# 3340.net
KiCad netlist of a schematic drawn in EAGLE
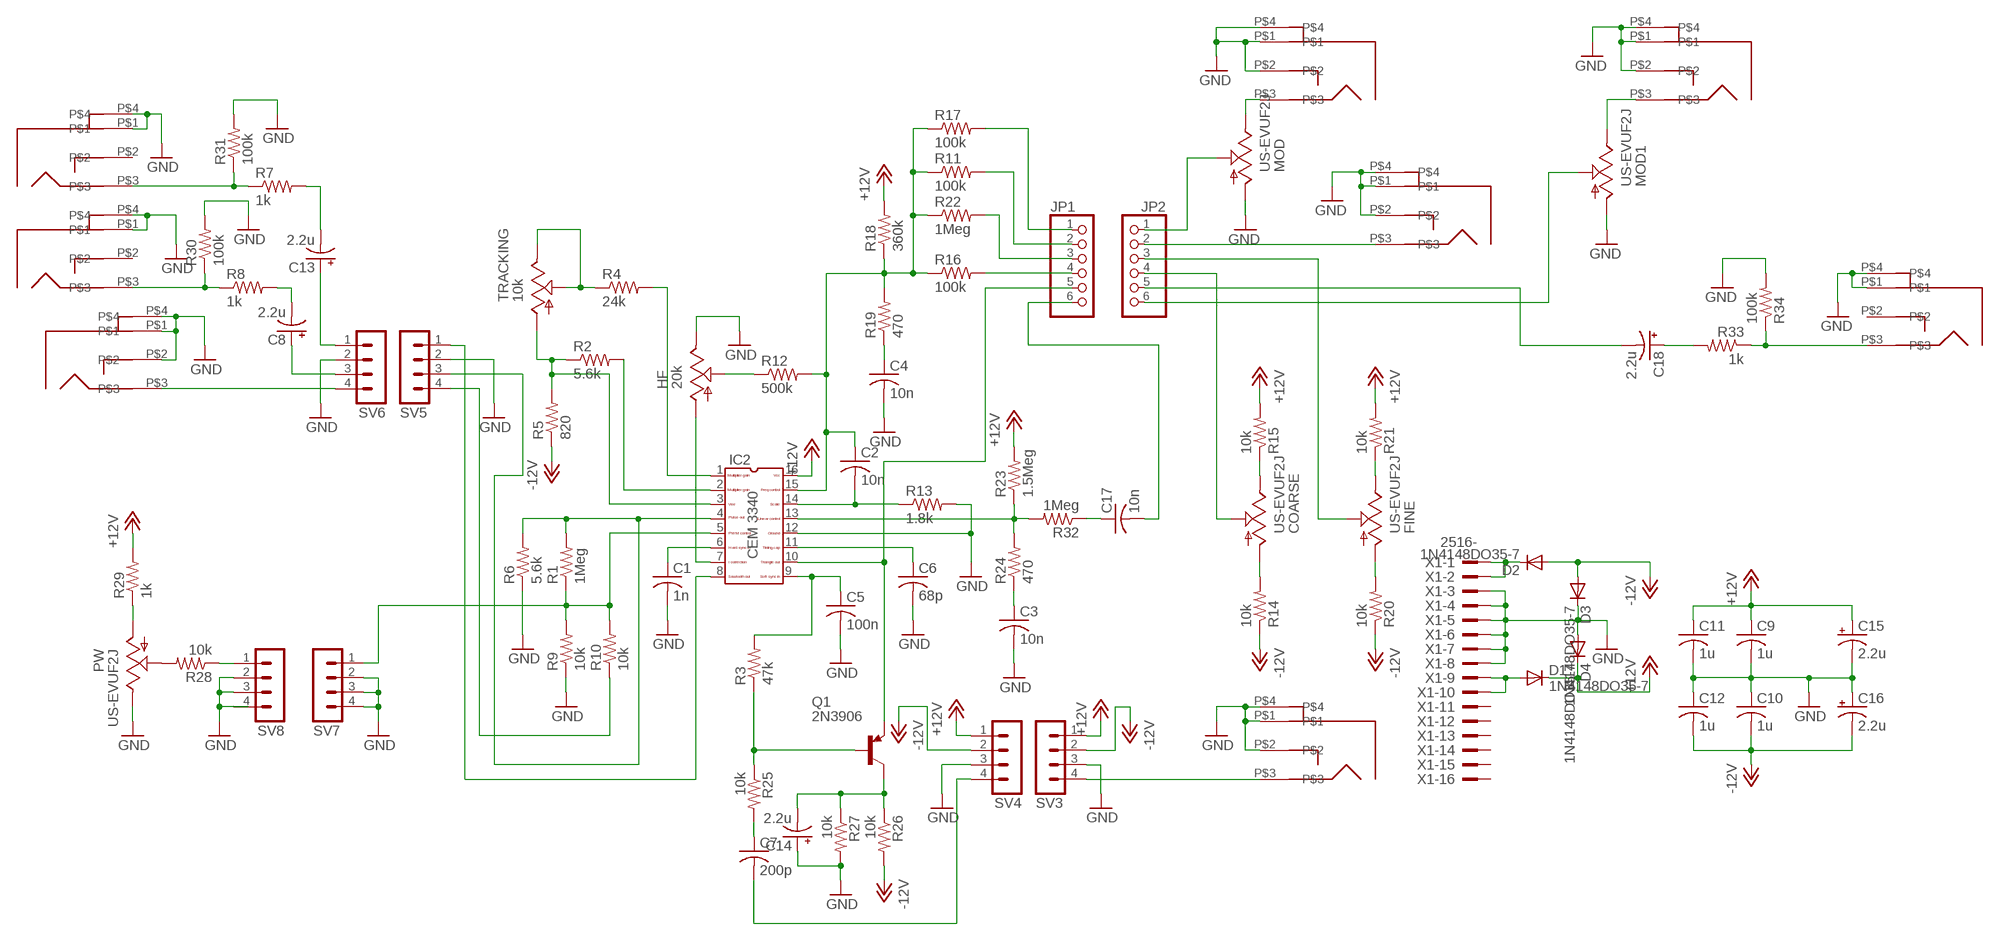
[diagram p0: schematic, sheet 1]

(export (version "E")
  (design (tool "Eeschema 10.0.6"))
  (components
    (comp (ref "C1")
      (value "1n")
      (footprint "eagle-import:C050-025X075")
      (libsource (lib "eagle-import") (part "C-US050-025X075"))
    )
    (comp (ref "C2")
      (value "10n")
      (footprint "eagle-import:C050-025X075")
      (libsource (lib "eagle-import") (part "C-US050-025X075"))
    )
    (comp (ref "C3")
      (value "10n")
      (footprint "eagle-import:C050-025X075")
      (libsource (lib "eagle-import") (part "C-US050-025X075"))
    )
    (comp (ref "C4")
      (value "10n")
      (footprint "eagle-import:C050-025X075")
      (libsource (lib "eagle-import") (part "C-US050-025X075"))
    )
    (comp (ref "C5")
      (value "100n")
      (footprint "eagle-import:C050-025X075")
      (libsource (lib "eagle-import") (part "C-US050-025X075"))
    )
    (comp (ref "C6")
      (value "68p")
      (footprint "eagle-import:C050-025X075")
      (libsource (lib "eagle-import") (part "C-US050-025X075"))
    )
    (comp (ref "C7")
      (value "200p")
      (footprint "eagle-import:C050-025X075")
      (libsource (lib "eagle-import") (part "C-US050-025X075"))
    )
    (comp (ref "C8")
      (value "2.2u")
      (footprint "eagle-import:E2,5-6")
      (libsource (lib "eagle-import") (part "CPOL-USE2.5-6"))
    )
    (comp (ref "C9")
      (value "1u")
      (footprint "eagle-import:C050-025X075")
      (libsource (lib "eagle-import") (part "C-US050-025X075"))
    )
    (comp (ref "C10")
      (value "1u")
      (footprint "eagle-import:C050-025X075")
      (libsource (lib "eagle-import") (part "C-US050-025X075"))
    )
    (comp (ref "C11")
      (value "1u")
      (footprint "eagle-import:C050-025X075")
      (libsource (lib "eagle-import") (part "C-US050-025X075"))
    )
    (comp (ref "C12")
      (value "1u")
      (footprint "eagle-import:C050-025X075")
      (libsource (lib "eagle-import") (part "C-US050-025X075"))
    )
    (comp (ref "C13")
      (value "2.2u")
      (footprint "eagle-import:E2,5-6")
      (libsource (lib "eagle-import") (part "CPOL-USE2.5-6"))
    )
    (comp (ref "C14")
      (value "2.2u")
      (footprint "eagle-import:E2,5-6")
      (libsource (lib "eagle-import") (part "CPOL-USE2.5-6"))
    )
    (comp (ref "C15")
      (value "2.2u")
      (footprint "eagle-import:E2,5-6")
      (libsource (lib "eagle-import") (part "CPOL-USE2.5-6"))
    )
    (comp (ref "C16")
      (value "2.2u")
      (footprint "eagle-import:E2,5-6")
      (libsource (lib "eagle-import") (part "CPOL-USE2.5-6"))
    )
    (comp (ref "C17")
      (value "10n")
      (footprint "eagle-import:C050-025X075")
      (libsource (lib "eagle-import") (part "C-US050-025X075"))
    )
    (comp (ref "C18")
      (value "2.2u")
      (footprint "eagle-import:E2,5-6")
      (libsource (lib "eagle-import") (part "CPOL-USE2.5-6"))
    )
    (comp (ref "COARSE")
      (value "US-EVUF2J")
      (footprint "eagle-import:EVUFXJ")
      (libsource (lib "eagle-import") (part "US-EVUF2J"))
    )
    (comp (ref "CVIN1")
      (value "PJ301BM")
      (footprint "eagle-import:PJ301BM")
      (libsource (lib "eagle-import") (part "PJ301BM"))
    )
    (comp (ref "CVIN2")
      (value "PJ301BM")
      (footprint "eagle-import:PJ301BM")
      (libsource (lib "eagle-import") (part "PJ301BM"))
    )
    (comp (ref "D1")
      (value "1N4148DO35-7")
      (footprint "eagle-import:DO35-7")
      (libsource (lib "eagle-import") (part "1N4148DO35-7"))
    )
    (comp (ref "D2")
      (value "1N4148DO35-7")
      (footprint "eagle-import:DO35-7")
      (libsource (lib "eagle-import") (part "1N4148DO35-7"))
    )
    (comp (ref "D3")
      (value "1N4148DO35-7")
      (footprint "eagle-import:DO35-7")
      (libsource (lib "eagle-import") (part "1N4148DO35-7"))
    )
    (comp (ref "D4")
      (value "1N4148DO35-7")
      (footprint "eagle-import:DO35-7")
      (libsource (lib "eagle-import") (part "1N4148DO35-7"))
    )
    (comp (ref "EXPMOD")
      (value "PJ301BM")
      (footprint "eagle-import:PJ301BM")
      (libsource (lib "eagle-import") (part "PJ301BM"))
    )
    (comp (ref "FINE")
      (value "US-EVUF2J")
      (footprint "eagle-import:EVUFXJ")
      (libsource (lib "eagle-import") (part "US-EVUF2J"))
    )
    (comp (ref "HF")
      (value "20k")
      (footprint "eagle-import:S64W")
      (libsource (lib "eagle-import") (part "TRIM_US-S64W"))
    )
    (comp (ref "IC2")
      (value "CEM3340")
      (footprint "eagle-import:DIL16")
      (libsource (lib "eagle-import") (part "CEM3340"))
    )
    (comp (ref "JP1")
      (value "PINHD-1X6")
      (footprint "eagle-import:1X06")
      (libsource (lib "eagle-import") (part "PINHD-1X6"))
    )
    (comp (ref "JP2")
      (value "PINHD-1X6")
      (footprint "eagle-import:1X06")
      (libsource (lib "eagle-import") (part "PINHD-1X6"))
    )
    (comp (ref "MOD")
      (value "US-EVUF2J")
      (footprint "eagle-import:EVUFXJ")
      (libsource (lib "eagle-import") (part "US-EVUF2J"))
    )
    (comp (ref "MOD1")
      (value "US-EVUF2J")
      (footprint "eagle-import:EVUFXJ")
      (libsource (lib "eagle-import") (part "US-EVUF2J"))
    )
    (comp (ref "PULSE")
      (value "PJ301BM")
      (footprint "eagle-import:PJ301BM")
      (libsource (lib "eagle-import") (part "PJ301BM"))
    )
    (comp (ref "PW")
      (value "US-EVUF2J")
      (footprint "eagle-import:EVUFXJ")
      (libsource (lib "eagle-import") (part "US-EVUF2J"))
    )
    (comp (ref "PWM")
      (value "PJ301BM")
      (footprint "eagle-import:PJ301BM")
      (libsource (lib "eagle-import") (part "PJ301BM"))
    )
    (comp (ref "Q1")
      (value "2N3906")
      (footprint "eagle-import:TO92")
      (libsource (lib "eagle-import") (part "2N3906"))
    )
    (comp (ref "R1")
      (value "1Meg")
      (footprint "eagle-import:0207_2V")
      (libsource (lib "eagle-import") (part "R-US_0207/2V"))
    )
    (comp (ref "R2")
      (value "5.6k")
      (footprint "eagle-import:0207_2V")
      (libsource (lib "eagle-import") (part "R-US_0207/2V"))
    )
    (comp (ref "R3")
      (value "47k")
      (footprint "eagle-import:0207_2V")
      (libsource (lib "eagle-import") (part "R-US_0207/2V"))
    )
    (comp (ref "R4")
      (value "24k")
      (footprint "eagle-import:0207_2V")
      (libsource (lib "eagle-import") (part "R-US_0207/2V"))
    )
    (comp (ref "R5")
      (value "820")
      (footprint "eagle-import:0207_2V")
      (libsource (lib "eagle-import") (part "R-US_0207/2V"))
    )
    (comp (ref "R6")
      (value "5.6k")
      (footprint "eagle-import:0207_2V")
      (libsource (lib "eagle-import") (part "R-US_0207/2V"))
    )
    (comp (ref "R7")
      (value "1k")
      (footprint "eagle-import:0207_7")
      (libsource (lib "eagle-import") (part "R-US_0207/7"))
    )
    (comp (ref "R8")
      (value "1k")
      (footprint "eagle-import:0207_7")
      (libsource (lib "eagle-import") (part "R-US_0207/7"))
    )
    (comp (ref "R9")
      (value "10k")
      (footprint "eagle-import:0207_2V")
      (libsource (lib "eagle-import") (part "R-US_0207/2V"))
    )
    (comp (ref "R10")
      (value "10k")
      (footprint "eagle-import:0207_2V")
      (libsource (lib "eagle-import") (part "R-US_0207/2V"))
    )
    (comp (ref "R11")
      (value "100k")
      (footprint "eagle-import:0207_2V")
      (libsource (lib "eagle-import") (part "R-US_0207/2V"))
    )
    (comp (ref "R12")
      (value "500k")
      (footprint "eagle-import:0207_2V")
      (libsource (lib "eagle-import") (part "R-US_0207/2V"))
    )
    (comp (ref "R13")
      (value "1.8k")
      (footprint "eagle-import:0207_2V")
      (libsource (lib "eagle-import") (part "R-US_0207/2V"))
    )
    (comp (ref "R14")
      (value "10k")
      (footprint "eagle-import:0207_7")
      (libsource (lib "eagle-import") (part "R-US_0207/7"))
    )
    (comp (ref "R15")
      (value "10k")
      (footprint "eagle-import:0207_7")
      (libsource (lib "eagle-import") (part "R-US_0207/7"))
    )
    (comp (ref "R16")
      (value "100k")
      (footprint "eagle-import:0207_2V")
      (libsource (lib "eagle-import") (part "R-US_0207/2V"))
    )
    (comp (ref "R17")
      (value "100k")
      (footprint "eagle-import:0207_2V")
      (libsource (lib "eagle-import") (part "R-US_0207/2V"))
    )
    (comp (ref "R18")
      (value "360k")
      (footprint "eagle-import:0207_2V")
      (libsource (lib "eagle-import") (part "R-US_0207/2V"))
    )
    (comp (ref "R19")
      (value "470")
      (footprint "eagle-import:0207_2V")
      (libsource (lib "eagle-import") (part "R-US_0207/2V"))
    )
    (comp (ref "R20")
      (value "10k")
      (footprint "eagle-import:0207_7")
      (libsource (lib "eagle-import") (part "R-US_0207/7"))
    )
    (comp (ref "R21")
      (value "10k")
      (footprint "eagle-import:0207_7")
      (libsource (lib "eagle-import") (part "R-US_0207/7"))
    )
    (comp (ref "R22")
      (value "1Meg")
      (footprint "eagle-import:0207_2V")
      (libsource (lib "eagle-import") (part "R-US_0207/2V"))
    )
    (comp (ref "R23")
      (value "1.5Meg")
      (footprint "eagle-import:0207_2V")
      (libsource (lib "eagle-import") (part "R-US_0207/2V"))
    )
    (comp (ref "R24")
      (value "470")
      (footprint "eagle-import:0207_2V")
      (libsource (lib "eagle-import") (part "R-US_0207/2V"))
    )
    (comp (ref "R25")
      (value "10k")
      (footprint "eagle-import:0207_2V")
      (libsource (lib "eagle-import") (part "R-US_0207/2V"))
    )
    (comp (ref "R26")
      (value "10k")
      (footprint "eagle-import:0207_2V")
      (libsource (lib "eagle-import") (part "R-US_0207/2V"))
    )
    (comp (ref "R27")
      (value "10k")
      (footprint "eagle-import:0207_2V")
      (libsource (lib "eagle-import") (part "R-US_0207/2V"))
    )
    (comp (ref "R28")
      (value "10k")
      (footprint "eagle-import:0207_7")
      (libsource (lib "eagle-import") (part "R-US_0207/7"))
    )
    (comp (ref "R29")
      (value "1k")
      (footprint "eagle-import:0207_7")
      (libsource (lib "eagle-import") (part "R-US_0207/7"))
    )
    (comp (ref "R30")
      (value "100k")
      (footprint "eagle-import:0207_7")
      (libsource (lib "eagle-import") (part "R-US_0207/7"))
    )
    (comp (ref "R31")
      (value "100k")
      (footprint "eagle-import:0207_7")
      (libsource (lib "eagle-import") (part "R-US_0207/7"))
    )
    (comp (ref "R32")
      (value "1Meg")
      (footprint "eagle-import:0207_2V")
      (libsource (lib "eagle-import") (part "R-US_0207/2V"))
    )
    (comp (ref "R33")
      (value "1k")
      (footprint "eagle-import:0207_7")
      (libsource (lib "eagle-import") (part "R-US_0207/7"))
    )
    (comp (ref "R34")
      (value "100k")
      (footprint "eagle-import:0207_7")
      (libsource (lib "eagle-import") (part "R-US_0207/7"))
    )
    (comp (ref "SAW")
      (value "PJ301BM")
      (footprint "eagle-import:PJ301BM")
      (libsource (lib "eagle-import") (part "PJ301BM"))
    )
    (comp (ref "SAW1")
      (value "PJ301BM")
      (footprint "eagle-import:PJ301BM")
      (libsource (lib "eagle-import") (part "PJ301BM"))
    )
    (comp (ref "SV3")
      (value "MA04-1")
      (footprint "eagle-import:MA04-1")
      (libsource (lib "eagle-import") (part "MA04-1"))
    )
    (comp (ref "SV4")
      (value "MA04-1")
      (footprint "eagle-import:MA04-1")
      (libsource (lib "eagle-import") (part "MA04-1"))
    )
    (comp (ref "SV5")
      (value "MA04-1")
      (footprint "eagle-import:MA04-1")
      (libsource (lib "eagle-import") (part "MA04-1"))
    )
    (comp (ref "SV6")
      (value "MA04-1")
      (footprint "eagle-import:MA04-1")
      (libsource (lib "eagle-import") (part "MA04-1"))
    )
    (comp (ref "SV7")
      (value "MA04-1")
      (footprint "eagle-import:MA04-1")
      (libsource (lib "eagle-import") (part "MA04-1"))
    )
    (comp (ref "SV8")
      (value "MA04-1")
      (footprint "eagle-import:MA04-1")
      (libsource (lib "eagle-import") (part "MA04-1"))
    )
    (comp (ref "SYNC")
      (value "PJ301BM")
      (footprint "eagle-import:PJ301BM")
      (libsource (lib "eagle-import") (part "PJ301BM"))
    )
    (comp (ref "TRACKING")
      (value "10k")
      (footprint "eagle-import:S64W")
      (libsource (lib "eagle-import") (part "TRIM_US-S64W"))
    )
    (comp (ref "X1")
      (value "2516-")
      (footprint "eagle-import:PAK100_2500-16")
      (libsource (lib "eagle-import") (part "2516-"))
    )
  )
  (nets
    (net (code "1") (name "+12V") (class "Default")
      (node (ref "C11") (pin "1") (pinfunction "1_1") (pintype "passive"))
      (node (ref "C15") (pin "+") (pinfunction "+_+") (pintype "passive"))
      (node (ref "C9") (pin "1") (pinfunction "1_1") (pintype "passive"))
      (node (ref "D1") (pin "C") (pinfunction "C_C") (pintype "passive"))
      (node (ref "D4") (pin "C") (pinfunction "C_C") (pintype "passive"))
      (node (ref "IC2") (pin "16") (pinfunction "16_16") (pintype "power_in"))
      (node (ref "R15") (pin "2") (pinfunction "2_2") (pintype "passive"))
      (node (ref "R18") (pin "2") (pinfunction "2_2") (pintype "passive"))
      (node (ref "R21") (pin "2") (pinfunction "2_2") (pintype "passive"))
      (node (ref "R23") (pin "2") (pinfunction "2_2") (pintype "passive"))
      (node (ref "R29") (pin "2") (pinfunction "2_2") (pintype "passive"))
      (node (ref "SV3") (pin "1") (pinfunction "1_1") (pintype "passive"))
      (node (ref "SV4") (pin "1") (pinfunction "1_1") (pintype "passive"))
    )
    (net (code "2") (name "-12V") (class "Default")
      (node (ref "C10") (pin "2") (pinfunction "2_2") (pintype "passive"))
      (node (ref "C12") (pin "2") (pinfunction "2_2") (pintype "passive"))
      (node (ref "C16") (pin "-") (pinfunction "-_-") (pintype "passive"))
      (node (ref "D2") (pin "A") (pinfunction "A_A") (pintype "passive"))
      (node (ref "D3") (pin "A") (pinfunction "A_A") (pintype "passive"))
      (node (ref "R14") (pin "1") (pinfunction "1_1") (pintype "passive"))
      (node (ref "R20") (pin "1") (pinfunction "1_1") (pintype "passive"))
      (node (ref "R26") (pin "2") (pinfunction "2_2") (pintype "passive"))
      (node (ref "R5") (pin "1") (pinfunction "1_1") (pintype "passive"))
      (node (ref "SV3") (pin "2") (pinfunction "2_2") (pintype "passive"))
      (node (ref "SV4") (pin "2") (pinfunction "2_2") (pintype "passive"))
    )
    (net (code "3") (name "GND") (class "Default")
      (node (ref "C1") (pin "2") (pinfunction "2_2") (pintype "passive"))
      (node (ref "C10") (pin "1") (pinfunction "1_1") (pintype "passive"))
      (node (ref "C11") (pin "2") (pinfunction "2_2") (pintype "passive"))
      (node (ref "C12") (pin "1") (pinfunction "1_1") (pintype "passive"))
      (node (ref "C14") (pin "+") (pinfunction "+_+") (pintype "passive"))
      (node (ref "C15") (pin "-") (pinfunction "-_-") (pintype "passive"))
      (node (ref "C16") (pin "+") (pinfunction "+_+") (pintype "passive"))
      (node (ref "C3") (pin "2") (pinfunction "2_2") (pintype "passive"))
      (node (ref "C4") (pin "2") (pinfunction "2_2") (pintype "passive"))
      (node (ref "C5") (pin "2") (pinfunction "2_2") (pintype "passive"))
      (node (ref "C6") (pin "2") (pinfunction "2_2") (pintype "passive"))
      (node (ref "C9") (pin "2") (pinfunction "2_2") (pintype "passive"))
      (node (ref "CVIN1") (pin "P$1") (pinfunction "P$1_P$1") (pintype "bidirectional"))
      (node (ref "CVIN1") (pin "P$2") (pinfunction "P$2_P$2") (pintype "bidirectional"))
      (node (ref "CVIN1") (pin "P$4") (pinfunction "P$4_P$4") (pintype "bidirectional"))
      (node (ref "CVIN2") (pin "P$1") (pinfunction "P$1_P$1") (pintype "bidirectional"))
      (node (ref "CVIN2") (pin "P$2") (pinfunction "P$2_P$2") (pintype "bidirectional"))
      (node (ref "CVIN2") (pin "P$4") (pinfunction "P$4_P$4") (pintype "bidirectional"))
      (node (ref "D3") (pin "C") (pinfunction "C_C") (pintype "passive"))
      (node (ref "D4") (pin "A") (pinfunction "A_A") (pintype "passive"))
      (node (ref "EXPMOD") (pin "P$1") (pinfunction "P$1_P$1") (pintype "bidirectional"))
      (node (ref "EXPMOD") (pin "P$2") (pinfunction "P$2_P$2") (pintype "bidirectional"))
      (node (ref "EXPMOD") (pin "P$4") (pinfunction "P$4_P$4") (pintype "bidirectional"))
      (node (ref "HF") (pin "E") (pinfunction "E_E") (pintype "passive"))
      (node (ref "IC2") (pin "12") (pinfunction "12_12") (pintype "power_in"))
      (node (ref "MOD") (pin "1") (pinfunction "A_1") (pintype "passive"))
      (node (ref "MOD1") (pin "1") (pinfunction "A_1") (pintype "passive"))
      (node (ref "PULSE") (pin "P$1") (pinfunction "P$1_P$1") (pintype "bidirectional"))
      (node (ref "PULSE") (pin "P$4") (pinfunction "P$4_P$4") (pintype "bidirectional"))
      (node (ref "PW") (pin "3") (pinfunction "E_3") (pintype "passive"))
      (node (ref "PWM") (pin "P$1") (pinfunction "P$1_P$1") (pintype "bidirectional"))
      (node (ref "PWM") (pin "P$2") (pinfunction "P$2_P$2") (pintype "bidirectional"))
      (node (ref "PWM") (pin "P$4") (pinfunction "P$4_P$4") (pintype "bidirectional"))
      (node (ref "R13") (pin "2") (pinfunction "2_2") (pintype "passive"))
      (node (ref "R27") (pin "2") (pinfunction "2_2") (pintype "passive"))
      (node (ref "R30") (pin "2") (pinfunction "2_2") (pintype "passive"))
      (node (ref "R31") (pin "2") (pinfunction "2_2") (pintype "passive"))
      (node (ref "R34") (pin "2") (pinfunction "2_2") (pintype "passive"))
      (node (ref "R6") (pin "1") (pinfunction "1_1") (pintype "passive"))
      (node (ref "R9") (pin "1") (pinfunction "1_1") (pintype "passive"))
      (node (ref "SAW") (pin "P$1") (pinfunction "P$1_P$1") (pintype "bidirectional"))
      (node (ref "SAW") (pin "P$4") (pinfunction "P$4_P$4") (pintype "bidirectional"))
      (node (ref "SAW1") (pin "P$1") (pinfunction "P$1_P$1") (pintype "bidirectional"))
      (node (ref "SAW1") (pin "P$4") (pinfunction "P$4_P$4") (pintype "bidirectional"))
      (node (ref "SV3") (pin "3") (pinfunction "3_3") (pintype "passive"))
      (node (ref "SV4") (pin "3") (pinfunction "3_3") (pintype "passive"))
      (node (ref "SV5") (pin "2") (pinfunction "2_2") (pintype "passive"))
      (node (ref "SV6") (pin "2") (pinfunction "2_2") (pintype "passive"))
      (node (ref "SV7") (pin "2") (pinfunction "2_2") (pintype "passive"))
      (node (ref "SV7") (pin "3") (pinfunction "3_3") (pintype "passive"))
      (node (ref "SV7") (pin "4") (pinfunction "4_4") (pintype "passive"))
      (node (ref "SV8") (pin "2") (pinfunction "2_2") (pintype "passive"))
      (node (ref "SV8") (pin "3") (pinfunction "3_3") (pintype "passive"))
      (node (ref "SYNC") (pin "P$1") (pinfunction "P$1_P$1") (pintype "bidirectional"))
      (node (ref "SYNC") (pin "P$2") (pinfunction "P$2_P$2") (pintype "bidirectional"))
      (node (ref "SYNC") (pin "P$4") (pinfunction "P$4_P$4") (pintype "bidirectional"))
      (node (ref "X1") (pin "3") (pinfunction "KL_3") (pintype "passive"))
      (node (ref "X1") (pin "4") (pinfunction "KL_4") (pintype "passive"))
      (node (ref "X1") (pin "5") (pinfunction "KL_5") (pintype "passive"))
      (node (ref "X1") (pin "6") (pinfunction "KL_6") (pintype "passive"))
      (node (ref "X1") (pin "7") (pinfunction "KL_7") (pintype "passive"))
      (node (ref "X1") (pin "8") (pinfunction "KL_8") (pintype "passive"))
    )
    (net (code "4") (name "Net-(C1-Pad1)") (class "Default")
      (node (ref "C1") (pin "1") (pinfunction "1_1") (pintype "passive"))
      (node (ref "IC2") (pin "6") (pinfunction "6_6") (pintype "input"))
    )
    (net (code "5") (name "Net-(C2-Pad1)") (class "Default")
      (node (ref "C2") (pin "1") (pinfunction "1_1") (pintype "passive"))
      (node (ref "IC2") (pin "15") (pinfunction "15_15") (pintype "input"))
      (node (ref "R11") (pin "1") (pinfunction "1_1") (pintype "passive"))
      (node (ref "R12") (pin "2") (pinfunction "2_2") (pintype "passive"))
      (node (ref "R16") (pin "1") (pinfunction "1_1") (pintype "passive"))
      (node (ref "R17") (pin "1") (pinfunction "1_1") (pintype "passive"))
      (node (ref "R18") (pin "1") (pinfunction "1_1") (pintype "passive"))
      (node (ref "R19") (pin "2") (pinfunction "2_2") (pintype "passive"))
      (node (ref "R22") (pin "1") (pinfunction "1_1") (pintype "passive"))
    )
    (net (code "6") (name "Net-(C2-Pad2)") (class "Default")
      (node (ref "C2") (pin "2") (pinfunction "2_2") (pintype "passive"))
      (node (ref "IC2") (pin "14") (pinfunction "14_14") (pintype "input"))
      (node (ref "R13") (pin "1") (pinfunction "1_1") (pintype "passive"))
    )
    (net (code "7") (name "Net-(C3-Pad1)") (class "Default")
      (node (ref "C3") (pin "1") (pinfunction "1_1") (pintype "passive"))
      (node (ref "R24") (pin "1") (pinfunction "1_1") (pintype "passive"))
    )
    (net (code "8") (name "Net-(C4-Pad1)") (class "Default")
      (node (ref "C4") (pin "1") (pinfunction "1_1") (pintype "passive"))
      (node (ref "R19") (pin "1") (pinfunction "1_1") (pintype "passive"))
    )
    (net (code "9") (name "Net-(C5-Pad1)") (class "Default")
      (node (ref "C5") (pin "1") (pinfunction "1_1") (pintype "passive"))
      (node (ref "IC2") (pin "9") (pinfunction "9_9") (pintype "input"))
      (node (ref "R3") (pin "2") (pinfunction "2_2") (pintype "passive"))
    )
    (net (code "10") (name "Net-(C6-Pad1)") (class "Default")
      (node (ref "C6") (pin "1") (pinfunction "1_1") (pintype "passive"))
      (node (ref "IC2") (pin "11") (pinfunction "11_11") (pintype "bidirectional"))
    )
    (net (code "11") (name "Net-(C7-Pad1)") (class "Default")
      (node (ref "C7") (pin "1") (pinfunction "1_1") (pintype "passive"))
      (node (ref "R25") (pin "2") (pinfunction "2_2") (pintype "passive"))
    )
    (net (code "12") (name "Net-(C7-Pad2)") (class "Default")
      (node (ref "C7") (pin "2") (pinfunction "2_2") (pintype "passive"))
      (node (ref "SV4") (pin "4") (pinfunction "4_4") (pintype "passive"))
    )
    (net (code "13") (name "Net-(C8-Pad+)") (class "Default")
      (node (ref "C8") (pin "+") (pinfunction "+_+") (pintype "passive"))
      (node (ref "SV6") (pin "3") (pinfunction "3_3") (pintype "passive"))
    )
    (net (code "14") (name "Net-(C8-Pad-)") (class "Default")
      (node (ref "C8") (pin "-") (pinfunction "-_-") (pintype "passive"))
      (node (ref "R8") (pin "2") (pinfunction "2_2") (pintype "passive"))
    )
    (net (code "15") (name "Net-(C13-Pad+)") (class "Default")
      (node (ref "C13") (pin "+") (pinfunction "+_+") (pintype "passive"))
      (node (ref "SV6") (pin "1") (pinfunction "1_1") (pintype "passive"))
    )
    (net (code "16") (name "Net-(C13-Pad-)") (class "Default")
      (node (ref "C13") (pin "-") (pinfunction "-_-") (pintype "passive"))
      (node (ref "R7") (pin "2") (pinfunction "2_2") (pintype "passive"))
    )
    (net (code "17") (name "Net-(C17-Pad1)") (class "Default")
      (node (ref "C17") (pin "1") (pinfunction "1_1") (pintype "passive"))
      (node (ref "R32") (pin "1") (pinfunction "1_1") (pintype "passive"))
    )
    (net (code "18") (name "Net-(C17-Pad2)") (class "Default")
      (node (ref "C17") (pin "2") (pinfunction "2_2") (pintype "passive"))
      (node (ref "JP1") (pin "6") (pinfunction "6_6") (pintype "passive"))
    )
    (net (code "19") (name "Net-(C18-Pad+)") (class "Default")
      (node (ref "C18") (pin "+") (pinfunction "+_+") (pintype "passive"))
      (node (ref "R33") (pin "2") (pinfunction "2_2") (pintype "passive"))
    )
    (net (code "20") (name "Net-(C18-Pad-)") (class "Default")
      (node (ref "C18") (pin "-") (pinfunction "-_-") (pintype "passive"))
      (node (ref "JP2") (pin "5") (pinfunction "5_5") (pintype "passive"))
    )
    (net (code "21") (name "Net-(COARSE-A)") (class "Default")
      (node (ref "COARSE") (pin "1") (pinfunction "A_1") (pintype "passive"))
      (node (ref "R14") (pin "2") (pinfunction "2_2") (pintype "passive"))
    )
    (net (code "22") (name "Net-(COARSE-E)") (class "Default")
      (node (ref "COARSE") (pin "3") (pinfunction "E_3") (pintype "passive"))
      (node (ref "R15") (pin "1") (pinfunction "1_1") (pintype "passive"))
    )
    (net (code "23") (name "Net-(COARSE-S)") (class "Default")
      (node (ref "COARSE") (pin "2") (pinfunction "S_2") (pintype "passive"))
      (node (ref "JP2") (pin "4") (pinfunction "4_4") (pintype "passive"))
    )
    (net (code "24") (name "Net-(CVIN1-PadP$3)") (class "Default")
      (node (ref "CVIN1") (pin "P$3") (pinfunction "P$3_P$3") (pintype "bidirectional"))
      (node (ref "JP2") (pin "2") (pinfunction "2_2") (pintype "passive"))
    )
    (net (code "25") (name "Net-(FINE-A)") (class "Default")
      (node (ref "FINE") (pin "1") (pinfunction "A_1") (pintype "passive"))
      (node (ref "R20") (pin "2") (pinfunction "2_2") (pintype "passive"))
    )
    (net (code "26") (name "Net-(FINE-E)") (class "Default")
      (node (ref "FINE") (pin "3") (pinfunction "E_3") (pintype "passive"))
      (node (ref "R21") (pin "1") (pinfunction "1_1") (pintype "passive"))
    )
    (net (code "27") (name "Net-(FINE-S)") (class "Default")
      (node (ref "FINE") (pin "2") (pinfunction "S_2") (pintype "passive"))
      (node (ref "JP2") (pin "3") (pinfunction "3_3") (pintype "passive"))
    )
    (net (code "28") (name "Net-(HF-PadA)") (class "Default")
      (node (ref "HF") (pin "A") (pinfunction "A_A") (pintype "passive"))
      (node (ref "IC2") (pin "7") (pinfunction "7_7") (pintype "bidirectional"))
    )
    (net (code "29") (name "Net-(HF-PadS)") (class "Default")
      (node (ref "HF") (pin "S") (pinfunction "S_S") (pintype "passive"))
      (node (ref "R12") (pin "1") (pinfunction "1_1") (pintype "passive"))
    )
    (net (code "30") (name "Net-(IC2-Pad1)") (class "Default")
      (node (ref "IC2") (pin "1") (pinfunction "1_1") (pintype "bidirectional"))
      (node (ref "R4") (pin "2") (pinfunction "2_2") (pintype "passive"))
    )
    (net (code "31") (name "Net-(IC2-Pad2)") (class "Default")
      (node (ref "IC2") (pin "2") (pinfunction "2_2") (pintype "bidirectional"))
      (node (ref "R2") (pin "2") (pinfunction "2_2") (pintype "passive"))
    )
    (net (code "32") (name "Net-(IC2-Pad3)") (class "Default")
      (node (ref "IC2") (pin "3") (pinfunction "3_3") (pintype "power_in"))
      (node (ref "R2") (pin "1") (pinfunction "1_1") (pintype "passive"))
      (node (ref "R5") (pin "2") (pinfunction "2_2") (pintype "passive"))
      (node (ref "TRACKING") (pin "A") (pinfunction "A_A") (pintype "passive"))
    )
    (net (code "33") (name "Net-(IC2-Pad4)") (class "Default")
      (node (ref "IC2") (pin "4") (pinfunction "4_4") (pintype "output"))
      (node (ref "R1") (pin "2") (pinfunction "2_2") (pintype "passive"))
      (node (ref "R6") (pin "2") (pinfunction "2_2") (pintype "passive"))
      (node (ref "SV5") (pin "3") (pinfunction "3_3") (pintype "passive"))
    )
    (net (code "34") (name "Net-(IC2-Pad5)") (class "Default")
      (node (ref "IC2") (pin "5") (pinfunction "5_5") (pintype "input"))
      (node (ref "R1") (pin "1") (pinfunction "1_1") (pintype "passive"))
      (node (ref "R10") (pin "2") (pinfunction "2_2") (pintype "passive"))
      (node (ref "R9") (pin "2") (pinfunction "2_2") (pintype "passive"))
      (node (ref "SV7") (pin "1") (pinfunction "1_1") (pintype "passive"))
    )
    (net (code "35") (name "Net-(IC2-Pad8)") (class "Default")
      (node (ref "IC2") (pin "8") (pinfunction "8_8") (pintype "output"))
      (node (ref "SV5") (pin "1") (pinfunction "1_1") (pintype "passive"))
    )
    (net (code "36") (name "Net-(IC2-Pad13)") (class "Default")
      (node (ref "IC2") (pin "13") (pinfunction "13_13") (pintype "input"))
      (node (ref "R23") (pin "1") (pinfunction "1_1") (pintype "passive"))
      (node (ref "R24") (pin "2") (pinfunction "2_2") (pintype "passive"))
      (node (ref "R32") (pin "2") (pinfunction "2_2") (pintype "passive"))
    )
    (net (code "37") (name "Net-(JP1-Pad1)") (class "Default")
      (node (ref "JP1") (pin "1") (pinfunction "1_1") (pintype "passive"))
      (node (ref "R17") (pin "2") (pinfunction "2_2") (pintype "passive"))
    )
    (net (code "38") (name "Net-(JP1-Pad2)") (class "Default")
      (node (ref "JP1") (pin "2") (pinfunction "2_2") (pintype "passive"))
      (node (ref "R11") (pin "2") (pinfunction "2_2") (pintype "passive"))
    )
    (net (code "39") (name "Net-(JP1-Pad3)") (class "Default")
      (node (ref "JP1") (pin "3") (pinfunction "3_3") (pintype "passive"))
      (node (ref "R22") (pin "2") (pinfunction "2_2") (pintype "passive"))
    )
    (net (code "40") (name "Net-(JP1-Pad4)") (class "Default")
      (node (ref "JP1") (pin "4") (pinfunction "4_4") (pintype "passive"))
      (node (ref "R16") (pin "2") (pinfunction "2_2") (pintype "passive"))
    )
    (net (code "41") (name "Net-(MOD-E)") (class "Default")
      (node (ref "EXPMOD") (pin "P$3") (pinfunction "P$3_P$3") (pintype "bidirectional"))
      (node (ref "MOD") (pin "3") (pinfunction "E_3") (pintype "passive"))
    )
    (net (code "42") (name "Net-(MOD-S)") (class "Default")
      (node (ref "JP2") (pin "1") (pinfunction "1_1") (pintype "passive"))
      (node (ref "MOD") (pin "2") (pinfunction "S_2") (pintype "passive"))
    )
    (net (code "43") (name "Net-(MOD1-E)") (class "Default")
      (node (ref "CVIN2") (pin "P$3") (pinfunction "P$3_P$3") (pintype "bidirectional"))
      (node (ref "MOD1") (pin "3") (pinfunction "E_3") (pintype "passive"))
    )
    (net (code "44") (name "Net-(MOD1-S)") (class "Default")
      (node (ref "JP2") (pin "6") (pinfunction "6_6") (pintype "passive"))
      (node (ref "MOD1") (pin "2") (pinfunction "S_2") (pintype "passive"))
    )
    (net (code "45") (name "Net-(PULSE-PadP$3)") (class "Default")
      (node (ref "PULSE") (pin "P$3") (pinfunction "P$3_P$3") (pintype "bidirectional"))
      (node (ref "R30") (pin "1") (pinfunction "1_1") (pintype "passive"))
      (node (ref "R8") (pin "1") (pinfunction "1_1") (pintype "passive"))
    )
    (net (code "46") (name "Net-(PW-A)") (class "Default")
      (node (ref "PW") (pin "1") (pinfunction "A_1") (pintype "passive"))
      (node (ref "R29") (pin "1") (pinfunction "1_1") (pintype "passive"))
    )
    (net (code "47") (name "Net-(PW-S)") (class "Default")
      (node (ref "PW") (pin "2") (pinfunction "S_2") (pintype "passive"))
      (node (ref "R28") (pin "2") (pinfunction "2_2") (pintype "passive"))
    )
    (net (code "48") (name "Net-(PWM-PadP$3)") (class "Default")
      (node (ref "PWM") (pin "P$3") (pinfunction "P$3_P$3") (pintype "bidirectional"))
      (node (ref "SV6") (pin "4") (pinfunction "4_4") (pintype "passive"))
    )
    (net (code "49") (name "Net-(Q1-B)") (class "Default")
      (node (ref "Q1") (pin "2") (pinfunction "B_2") (pintype "passive"))
      (node (ref "R25") (pin "1") (pinfunction "1_1") (pintype "passive"))
      (node (ref "R3") (pin "1") (pinfunction "1_1") (pintype "passive"))
    )
    (net (code "50") (name "Net-(Q1-C)") (class "Default")
      (node (ref "C14") (pin "-") (pinfunction "-_-") (pintype "passive"))
      (node (ref "Q1") (pin "1") (pinfunction "C_1") (pintype "passive"))
      (node (ref "R26") (pin "1") (pinfunction "1_1") (pintype "passive"))
      (node (ref "R27") (pin "1") (pinfunction "1_1") (pintype "passive"))
    )
    (net (code "51") (name "Net-(Q1-E)") (class "Default")
      (node (ref "IC2") (pin "10") (pinfunction "10_10") (pintype "output"))
      (node (ref "JP1") (pin "5") (pinfunction "5_5") (pintype "passive"))
      (node (ref "Q1") (pin "3") (pinfunction "E_3") (pintype "passive"))
    )
    (net (code "52") (name "Net-(R4-Pad1)") (class "Default")
      (node (ref "R4") (pin "1") (pinfunction "1_1") (pintype "passive"))
      (node (ref "TRACKING") (pin "E") (pinfunction "E_E") (pintype "passive"))
      (node (ref "TRACKING") (pin "S") (pinfunction "S_S") (pintype "passive"))
    )
    (net (code "53") (name "Net-(R10-Pad1)") (class "Default")
      (node (ref "R10") (pin "1") (pinfunction "1_1") (pintype "passive"))
      (node (ref "SV5") (pin "4") (pinfunction "4_4") (pintype "passive"))
    )
    (net (code "54") (name "Net-(R28-Pad1)") (class "Default")
      (node (ref "R28") (pin "1") (pinfunction "1_1") (pintype "passive"))
      (node (ref "SV8") (pin "1") (pinfunction "1_1") (pintype "passive"))
    )
    (net (code "55") (name "Net-(R31-Pad1)") (class "Default")
      (node (ref "R31") (pin "1") (pinfunction "1_1") (pintype "passive"))
      (node (ref "R7") (pin "1") (pinfunction "1_1") (pintype "passive"))
      (node (ref "SAW") (pin "P$3") (pinfunction "P$3_P$3") (pintype "bidirectional"))
    )
    (net (code "56") (name "Net-(R33-Pad1)") (class "Default")
      (node (ref "R33") (pin "1") (pinfunction "1_1") (pintype "passive"))
      (node (ref "R34") (pin "1") (pinfunction "1_1") (pintype "passive"))
      (node (ref "SAW1") (pin "P$3") (pinfunction "P$3_P$3") (pintype "bidirectional"))
    )
    (net (code "57") (name "Net-(SV3-Pad4)") (class "Default")
      (node (ref "SV3") (pin "4") (pinfunction "4_4") (pintype "passive"))
      (node (ref "SYNC") (pin "P$3") (pinfunction "P$3_P$3") (pintype "bidirectional"))
    )
    (net (code "58") (name "Net-(X1A-KL)") (class "Default")
      (node (ref "D2") (pin "C") (pinfunction "C_C") (pintype "passive"))
      (node (ref "X1") (pin "1") (pinfunction "KL_1") (pintype "passive"))
      (node (ref "X1") (pin "2") (pinfunction "KL_2") (pintype "passive"))
    )
    (net (code "59") (name "Net-(X1B-KL)") (class "Default")
      (node (ref "D1") (pin "A") (pinfunction "A_A") (pintype "passive"))
      (node (ref "X1") (pin "10") (pinfunction "KL_10") (pintype "passive"))
      (node (ref "X1") (pin "9") (pinfunction "KL_9") (pintype "passive"))
    )
    (net (code "60") (name "unconnected-(PULSE-PadP$2)") (class "Default")
      (node (ref "PULSE") (pin "P$2") (pinfunction "P$2_P$2") (pintype "bidirectional"))
    )
    (net (code "61") (name "unconnected-(SAW-PadP$2)") (class "Default")
      (node (ref "SAW") (pin "P$2") (pinfunction "P$2_P$2") (pintype "bidirectional"))
    )
    (net (code "62") (name "unconnected-(SAW1-PadP$2)") (class "Default")
      (node (ref "SAW1") (pin "P$2") (pinfunction "P$2_P$2") (pintype "bidirectional"))
    )
    (net (code "63") (name "unconnected-(SV8-Pad4)") (class "Default")
      (node (ref "SV8") (pin "4") (pinfunction "4_4") (pintype "passive"))
    )
    (net (code "64") (name "unconnected-(X1C-KL-Pad11)") (class "Default")
      (node (ref "X1") (pin "11") (pinfunction "KL_11") (pintype "passive"))
    )
    (net (code "65") (name "unconnected-(X1D-KL-Pad12)") (class "Default")
      (node (ref "X1") (pin "12") (pinfunction "KL_12") (pintype "passive"))
    )
    (net (code "66") (name "unconnected-(X1E-KL-Pad13)") (class "Default")
      (node (ref "X1") (pin "13") (pinfunction "KL_13") (pintype "passive"))
    )
    (net (code "67") (name "unconnected-(X1F-KL-Pad14)") (class "Default")
      (node (ref "X1") (pin "14") (pinfunction "KL_14") (pintype "passive"))
    )
    (net (code "68") (name "unconnected-(X1G-KL-Pad15)") (class "Default")
      (node (ref "X1") (pin "15") (pinfunction "KL_15") (pintype "passive"))
    )
    (net (code "69") (name "unconnected-(X1H-KL-Pad16)") (class "Default")
      (node (ref "X1") (pin "16") (pinfunction "KL_16") (pintype "passive"))
    )
  )
)
